# SDCARD_MRAM.net
KiCad netlist of a schematic drawn in Altium Designer
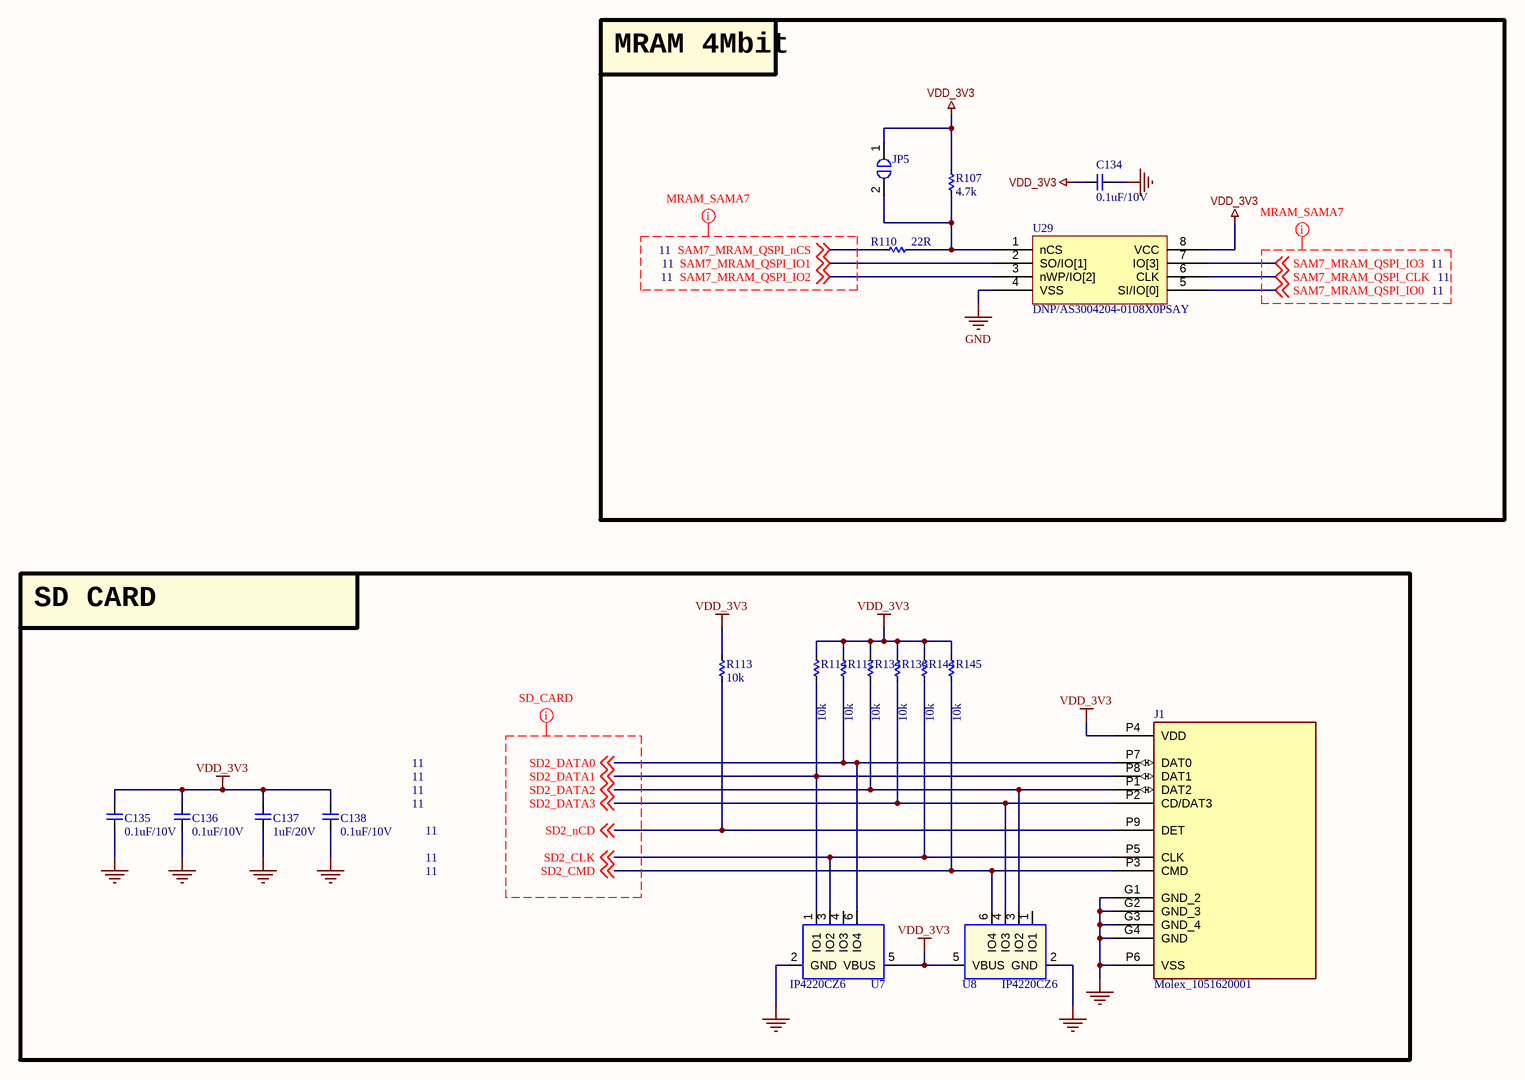
[diagram p0: SDCARD_MRAM.SchDoc]

(export (version "E")
  (design (tool "Eeschema 10.0.6"))
  (components
    (comp (ref "C134")
      (value "0.1uF/10V")
      (footprint "CAP_C_1005X50_L")
      (description "CAP")
      (libsource (lib "LABLIB") (part "_CAP_C_2"))
    )
    (comp (ref "C135")
      (value "0.1uF/10V")
      (footprint "CAP_C_1005X50_L")
      (description "CAP")
      (libsource (lib "LABLIB") (part "_CAP_C_2"))
    )
    (comp (ref "C136")
      (value "0.1uF/10V")
      (footprint "CAP_C_1005X50_L")
      (description "CAP")
      (libsource (lib "LABLIB") (part "_CAP_C_2"))
    )
    (comp (ref "C137")
      (value "1uF/20V")
      (footprint "CAP_C_1005X50_L")
      (description "CAP CHIP")
      (libsource (lib "IFBschelib") (part "_CAP_C_2"))
    )
    (comp (ref "C138")
      (value "0.1uF/10V")
      (footprint "CAP_C_1005X50_L")
      (description "CAP")
      (libsource (lib "LABLIB") (part "_CAP_C_2"))
    )
    (comp (ref "J1")
      (value "Molex_1051620001")
      (footprint "Molex_1051620001")
      (description "9 (8 + 1) Position Card Connector Secure Digital - microSDâ„¢ Surface Mount, Right Angle Gold")
      (fields (field (name "MF") "Molex") (field (name "MP") "1051620001"))
      (libsource (lib "IFBschelib") (part "Molex_1051620001"))
    )
    (comp (ref "JP5") (value "~") (footprint "JUMPER_1608") (libsource (lib "LABLIB") (part "JUMPER_1_1")))
    (comp (ref "R107")
      (value "4.7k")
      (footprint "RES_C_1005x30_L")
      (description "RES")
      (libsource (lib "IFBschelib") (part "_RES_B_2"))
    )
    (comp (ref "R110")
      (value "22R")
      (footprint "RES_C_1005x30_L")
      (description "RES")
      (libsource (lib "LABLIB") (part "_RES_B_2"))
    )
    (comp (ref "R113")
      (value "10k")
      (footprint "RES_C_1005x30_L")
      (description "RES")
      (libsource (lib "LABLIB") (part "_RES_B_2"))
    )
    (comp (ref "R114")
      (value "10k")
      (footprint "RES_C_1005x30_L")
      (description "RES")
      (libsource (lib "LABLIB") (part "_RES_B_2"))
    )
    (comp (ref "R117")
      (value "10k")
      (footprint "RES_C_1005x30_L")
      (description "RES")
      (libsource (lib "LABLIB") (part "_RES_B_2"))
    )
    (comp (ref "R134")
      (value "10k")
      (footprint "RES_C_1005x30_L")
      (description "RES")
      (libsource (lib "LABLIB") (part "_RES_B_2"))
    )
    (comp (ref "R136")
      (value "10k")
      (footprint "RES_C_1005x30_L")
      (description "RES")
      (libsource (lib "LABLIB") (part "_RES_B_2"))
    )
    (comp (ref "R144")
      (value "10k")
      (footprint "RES_C_1005x30_L")
      (description "RES")
      (libsource (lib "LABLIB") (part "_RES_B_2"))
    )
    (comp (ref "R145")
      (value "10k")
      (footprint "RES_C_1005x30_L")
      (description "RES")
      (libsource (lib "LABLIB") (part "_RES_B_2"))
    )
    (comp (ref "U7")
      (value "IP4220CZ6")
      (footprint "SOT95P280X145-6N")
      (libsource (lib "LABLIB") (part "IP4220CZ6_0"))
    )
    (comp (ref "U8")
      (value "IP4220CZ6")
      (footprint "SOT95P280X145-6N")
      (libsource (lib "") (part "IP4220CZ6_0_1"))
    )
    (comp (ref "U29")
      (value "DNP/AS3004204-0108X0PSAY")
      (footprint "SOIC127P790X216-8")
      (libsource (lib "LABLIB") (part "IC_RAM_AS3004204-0108X0PSAY"))
    )
  )
  (nets
    (net (code "1") (name "GND") (class "Default")
      (node (ref "C134") (pin "1") (pinfunction "1_1") (pintype "passive"))
      (node (ref "C135") (pin "1") (pinfunction "1_1") (pintype "passive"))
      (node (ref "C136") (pin "1") (pinfunction "1_1") (pintype "passive"))
      (node (ref "C137") (pin "1") (pinfunction "1_1") (pintype "passive"))
      (node (ref "C138") (pin "1") (pinfunction "1_1") (pintype "passive"))
      (node (ref "J1") (pin "G1") (pinfunction "GND_2_G1") (pintype "passive"))
      (node (ref "J1") (pin "G2") (pinfunction "GND_3_G2") (pintype "passive"))
      (node (ref "J1") (pin "G3") (pinfunction "GND_4_G3") (pintype "passive"))
      (node (ref "J1") (pin "G4") (pinfunction "GND_G4") (pintype "passive"))
      (node (ref "J1") (pin "P6") (pinfunction "VSS_P6") (pintype "passive"))
      (node (ref "U29") (pin "4") (pinfunction "VSS_4") (pintype "passive"))
      (node (ref "U7") (pin "2") (pinfunction "GND_2") (pintype "passive"))
      (node (ref "U8") (pin "2") (pinfunction "GND_2") (pintype "passive"))
    )
    (net (code "2") (name "Net-(U29-nCS)") (class "Default")
      (node (ref "JP5") (pin "2") (pinfunction "2_2") (pintype "passive"))
      (node (ref "R107") (pin "1") (pinfunction "1_1") (pintype "passive"))
      (node (ref "R110") (pin "2") (pinfunction "2_2") (pintype "passive"))
      (node (ref "U29") (pin "1") (pinfunction "nCS_1") (pintype "passive"))
    )
    (net (code "3") (name "SAM7_MRAM_QSPI_CLK") (class "Default")
      (node (ref "U29") (pin "6") (pinfunction "CLK_6") (pintype "passive"))
    )
    (net (code "4") (name "SAM7_MRAM_QSPI_IO0") (class "Default")
      (node (ref "U29") (pin "5") (pinfunction "SI/IO[0]_5") (pintype "passive"))
    )
    (net (code "5") (name "SAM7_MRAM_QSPI_IO1") (class "Default")
      (node (ref "U29") (pin "2") (pinfunction "SO/IO[1]_2") (pintype "passive"))
    )
    (net (code "6") (name "SAM7_MRAM_QSPI_IO2") (class "Default")
      (node (ref "U29") (pin "3") (pinfunction "nWP/IO[2]_3") (pintype "passive"))
    )
    (net (code "7") (name "SAM7_MRAM_QSPI_IO3") (class "Default")
      (node (ref "U29") (pin "7") (pinfunction "IO[3]_7") (pintype "passive"))
    )
    (net (code "8") (name "SAM7_MRAM_QSPI_nCS") (class "Default")
      (node (ref "R110") (pin "1") (pinfunction "1_1") (pintype "passive"))
    )
    (net (code "9") (name "SD2_CLK") (class "Default")
      (node (ref "J1") (pin "P5") (pinfunction "CLK_P5") (pintype "passive"))
      (node (ref "R144") (pin "1") (pinfunction "1_1") (pintype "passive"))
      (node (ref "U7") (pin "3") (pinfunction "IO2_3") (pintype "passive"))
    )
    (net (code "10") (name "SD2_CMD") (class "Default")
      (node (ref "J1") (pin "P3") (pinfunction "CMD_P3") (pintype "passive"))
      (node (ref "R145") (pin "1") (pinfunction "1_1") (pintype "passive"))
      (node (ref "U8") (pin "6") (pinfunction "IO4_6") (pintype "passive"))
    )
    (net (code "11") (name "SD2_DATA0") (class "Default")
      (node (ref "J1") (pin "P7") (pinfunction "DAT0_P7") (pintype "bidirectional"))
      (node (ref "R117") (pin "1") (pinfunction "1_1") (pintype "passive"))
      (node (ref "U7") (pin "6") (pinfunction "IO4_6") (pintype "passive"))
    )
    (net (code "12") (name "SD2_DATA1") (class "Default")
      (node (ref "J1") (pin "P8") (pinfunction "DAT1_P8") (pintype "bidirectional"))
      (node (ref "R114") (pin "1") (pinfunction "1_1") (pintype "passive"))
      (node (ref "U7") (pin "1") (pinfunction "IO1_1") (pintype "passive"))
    )
    (net (code "13") (name "SD2_DATA2") (class "Default")
      (node (ref "J1") (pin "P1") (pinfunction "DAT2_P1") (pintype "bidirectional"))
      (node (ref "R134") (pin "1") (pinfunction "1_1") (pintype "passive"))
      (node (ref "U8") (pin "3") (pinfunction "IO2_3") (pintype "passive"))
    )
    (net (code "14") (name "SD2_DATA3") (class "Default")
      (node (ref "J1") (pin "P2") (pinfunction "CD/DAT3_P2") (pintype "passive"))
      (node (ref "R136") (pin "1") (pinfunction "1_1") (pintype "passive"))
      (node (ref "U8") (pin "4") (pinfunction "IO3_4") (pintype "passive"))
    )
    (net (code "15") (name "SD2_nCD") (class "Default")
      (node (ref "J1") (pin "P9") (pinfunction "DET_P9") (pintype "passive"))
      (node (ref "R113") (pin "1") (pinfunction "1_1") (pintype "passive"))
    )
    (net (code "16") (name "VDD_3V3") (class "Default")
      (node (ref "C134") (pin "2") (pinfunction "2_2") (pintype "passive"))
      (node (ref "C135") (pin "2") (pinfunction "2_2") (pintype "passive"))
      (node (ref "C136") (pin "2") (pinfunction "2_2") (pintype "passive"))
      (node (ref "C137") (pin "2") (pinfunction "2_2") (pintype "passive"))
      (node (ref "C138") (pin "2") (pinfunction "2_2") (pintype "passive"))
      (node (ref "J1") (pin "P4") (pinfunction "VDD_P4") (pintype "power_in"))
      (node (ref "JP5") (pin "1") (pinfunction "1_1") (pintype "passive"))
      (node (ref "R107") (pin "2") (pinfunction "2_2") (pintype "passive"))
      (node (ref "R113") (pin "2") (pinfunction "2_2") (pintype "passive"))
      (node (ref "R114") (pin "2") (pinfunction "2_2") (pintype "passive"))
      (node (ref "R117") (pin "2") (pinfunction "2_2") (pintype "passive"))
      (node (ref "R134") (pin "2") (pinfunction "2_2") (pintype "passive"))
      (node (ref "R136") (pin "2") (pinfunction "2_2") (pintype "passive"))
      (node (ref "R144") (pin "2") (pinfunction "2_2") (pintype "passive"))
      (node (ref "R145") (pin "2") (pinfunction "2_2") (pintype "passive"))
      (node (ref "U29") (pin "8") (pinfunction "VCC_8") (pintype "passive"))
      (node (ref "U7") (pin "5") (pinfunction "VBUS_5") (pintype "passive"))
      (node (ref "U8") (pin "5") (pinfunction "VBUS_5") (pintype "passive"))
    )
    (net (code "17") (name "unconnected-(U7-IO3-Pad4)") (class "Default")
      (node (ref "U7") (pin "4") (pinfunction "IO3_4") (pintype "passive"))
    )
    (net (code "18") (name "unconnected-(U8-IO1-Pad1)") (class "Default")
      (node (ref "U8") (pin "1") (pinfunction "IO1_1") (pintype "passive"))
    )
  )
)
